# 171-5783_Redux.net
KiCad netlist of a schematic drawn in Altium Designer
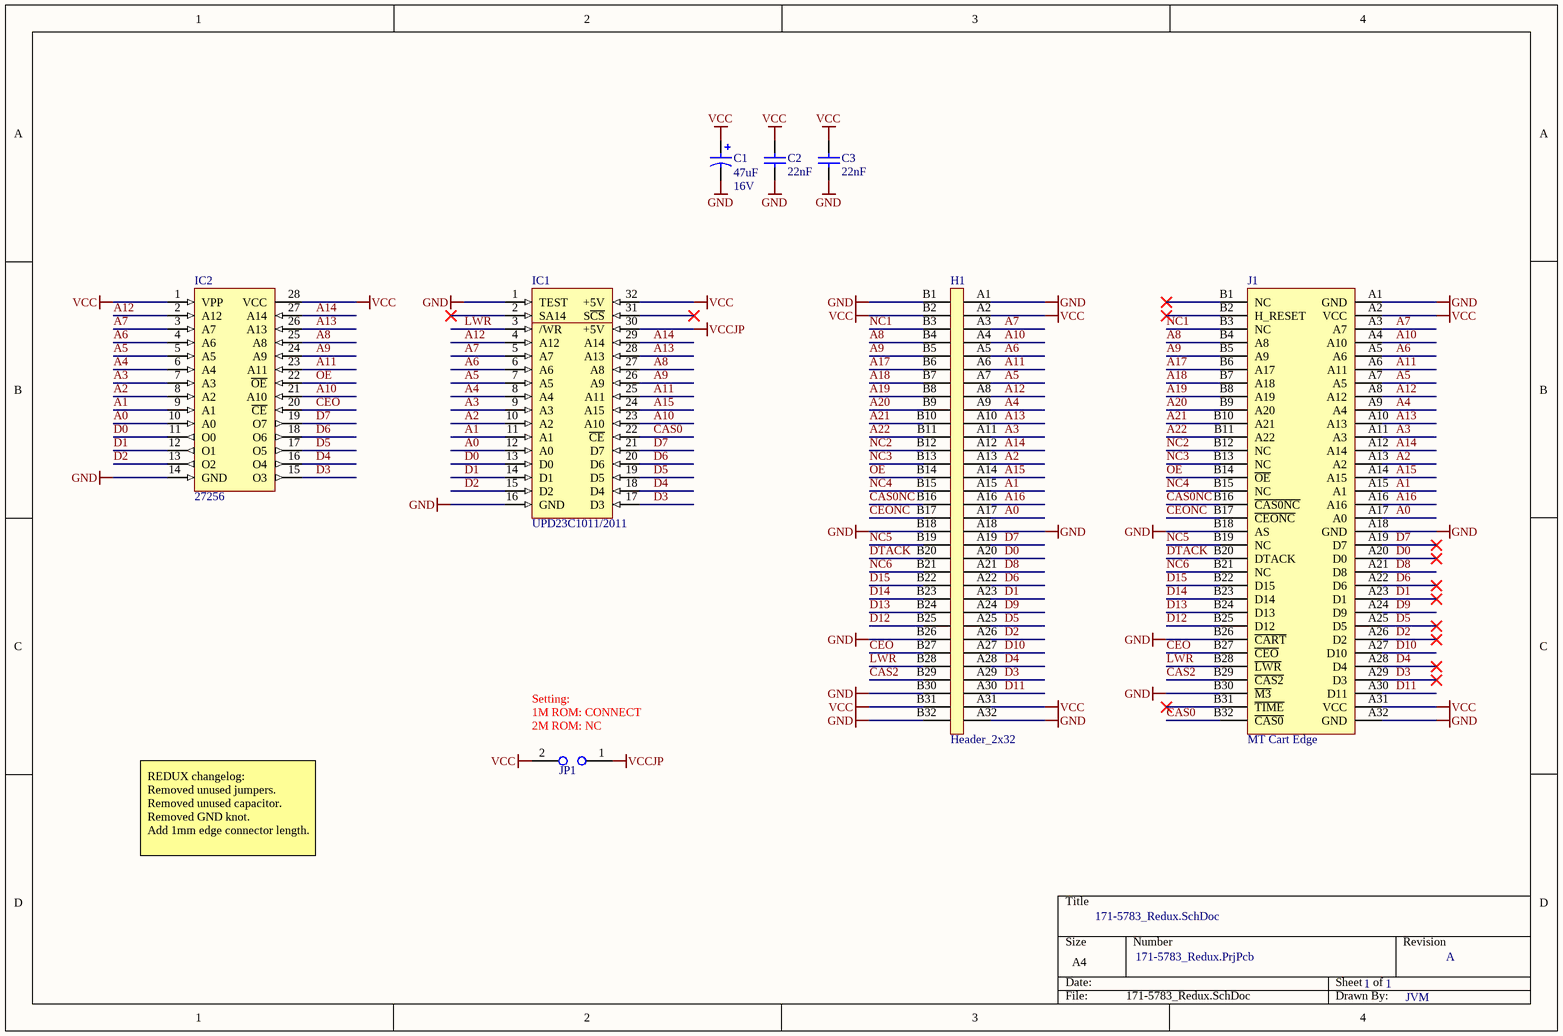
[diagram p0: 171-5783_Redux.SchDoc]

(export (version "E")
  (design (tool "Eeschema 10.0.6"))
  (components
    (comp (ref "C1")
      (value "47uF")
      (footprint "CapPol Mirror")
      (description "Polarized Capacitor, 2.54mm Pitch, 5mm Width, mirrored")
      (fields (field (name "VOLTAGE") "16V") (field (name "Comment") "Cap2.54P5.0D"))
      (libsource (lib "171-5782") (part "Cap2.54P5.0D_mirror"))
    )
    (comp (ref "C2")
      (value "22nF")
      (footprint "CapCer")
      (description "Capacitor (THT), Ceramic, 5.08mm Pitch")
      (fields (field (name "Comment") "CapCer"))
      (libsource (lib "171-5782") (part "CapCer"))
    )
    (comp (ref "C3")
      (value "22nF")
      (footprint "CapCer")
      (description "Capacitor (THT), Ceramic, 5.08mm Pitch")
      (fields (field (name "Comment") "CapCer"))
      (libsource (lib "171-5782") (part "CapCer"))
    )
    (comp (ref "H1")
      (value "Header_2x32")
      (footprint "Header_2x32")
      (libsource (lib "171-5782") (part "Header_2x32"))
    )
    (comp (ref "IC1")
      (value "UPD23C1011/2011")
      (footprint "UPD23C1011/2011")
      (description "SMS Mapper Mask Rom, Dual footprint")
      (libsource (lib "171-5782") (part "UPD23C1011/2011"))
    )
    (comp (ref "IC2")
      (value "27256")
      (footprint "27256")
      (description "256K EPROM")
      (libsource (lib "171-5782") (part "27256"))
    )
    (comp (ref "J1")
      (value "MT Cart Edge")
      (footprint "MT_Cart_Edge")
      (libsource (lib "171-5782") (part "MT_CART_EDGE_CON"))
    )
    (comp (ref "JP1")
      (value "SolderBridge")
      (footprint "SOLDER_BRIDGE")
      (description "Solder Bridge")
      (libsource (lib "171-5782") (part "SolderBridge"))
    )
  )
  (nets
    (net (code "1") (name "/A0") (class "Default")
      (node (ref "H1") (pin "A17") (pintype "passive"))
      (node (ref "IC1") (pin "12") (pinfunction "A0_12") (pintype "input"))
      (node (ref "IC2") (pin "10") (pinfunction "A0_10") (pintype "input"))
      (node (ref "J1") (pin "A17") (pinfunction "A0_A17") (pintype "passive"))
    )
    (net (code "2") (name "/A1") (class "Default")
      (node (ref "H1") (pin "A15") (pintype "passive"))
      (node (ref "IC1") (pin "11") (pinfunction "A1_11") (pintype "input"))
      (node (ref "IC2") (pin "9") (pinfunction "A1_9") (pintype "input"))
      (node (ref "J1") (pin "A15") (pinfunction "A1_A15") (pintype "passive"))
    )
    (net (code "3") (name "/A2") (class "Default")
      (node (ref "H1") (pin "A13") (pintype "passive"))
      (node (ref "IC1") (pin "10") (pinfunction "A2_10") (pintype "input"))
      (node (ref "IC2") (pin "8") (pinfunction "A2_8") (pintype "input"))
      (node (ref "J1") (pin "A13") (pinfunction "A2_A13") (pintype "passive"))
    )
    (net (code "4") (name "/A3") (class "Default")
      (node (ref "H1") (pin "A11") (pintype "passive"))
      (node (ref "IC1") (pin "9") (pinfunction "A3_9") (pintype "input"))
      (node (ref "IC2") (pin "7") (pinfunction "A3_7") (pintype "input"))
      (node (ref "J1") (pin "A11") (pinfunction "A3_A11") (pintype "passive"))
    )
    (net (code "5") (name "/A4") (class "Default")
      (node (ref "H1") (pin "A9") (pintype "passive"))
      (node (ref "IC1") (pin "8") (pinfunction "A4_8") (pintype "input"))
      (node (ref "IC2") (pin "6") (pinfunction "A4_6") (pintype "input"))
      (node (ref "J1") (pin "A9") (pinfunction "A4_A9") (pintype "passive"))
    )
    (net (code "6") (name "/A5") (class "Default")
      (node (ref "H1") (pin "A7") (pintype "passive"))
      (node (ref "IC1") (pin "7") (pinfunction "A5_7") (pintype "input"))
      (node (ref "IC2") (pin "5") (pinfunction "A5_5") (pintype "input"))
      (node (ref "J1") (pin "A7") (pinfunction "A5_A7") (pintype "passive"))
    )
    (net (code "7") (name "/A6") (class "Default")
      (node (ref "H1") (pin "A5") (pintype "passive"))
      (node (ref "IC1") (pin "6") (pinfunction "A6_6") (pintype "input"))
      (node (ref "IC2") (pin "4") (pinfunction "A6_4") (pintype "input"))
      (node (ref "J1") (pin "A5") (pinfunction "A6_A5") (pintype "passive"))
    )
    (net (code "8") (name "/A7") (class "Default")
      (node (ref "H1") (pin "A3") (pintype "passive"))
      (node (ref "IC1") (pin "5") (pinfunction "A7_5") (pintype "input"))
      (node (ref "IC2") (pin "3") (pinfunction "A7_3") (pintype "input"))
      (node (ref "J1") (pin "A3") (pinfunction "A7_A3") (pintype "passive"))
    )
    (net (code "9") (name "/A8") (class "Default")
      (node (ref "H1") (pin "B4") (pintype "passive"))
      (node (ref "IC1") (pin "27") (pinfunction "A8_27") (pintype "input"))
      (node (ref "IC2") (pin "25") (pinfunction "A8_25") (pintype "input"))
      (node (ref "J1") (pin "B4") (pinfunction "A8_B4") (pintype "passive"))
    )
    (net (code "10") (name "/A9") (class "Default")
      (node (ref "H1") (pin "B5") (pintype "passive"))
      (node (ref "IC1") (pin "26") (pinfunction "A9_26") (pintype "input"))
      (node (ref "IC2") (pin "24") (pinfunction "A9_24") (pintype "input"))
      (node (ref "J1") (pin "B5") (pinfunction "A9_B5") (pintype "passive"))
    )
    (net (code "11") (name "/A10") (class "Default")
      (node (ref "H1") (pin "A4") (pintype "passive"))
      (node (ref "IC1") (pin "23") (pinfunction "A10_23") (pintype "input"))
      (node (ref "IC2") (pin "21") (pinfunction "A10_21") (pintype "input"))
      (node (ref "J1") (pin "A4") (pinfunction "A10_A4") (pintype "passive"))
    )
    (net (code "12") (name "/A11") (class "Default")
      (node (ref "H1") (pin "A6") (pintype "passive"))
      (node (ref "IC1") (pin "25") (pinfunction "A11_25") (pintype "input"))
      (node (ref "IC2") (pin "23") (pinfunction "A11_23") (pintype "input"))
      (node (ref "J1") (pin "A6") (pinfunction "A11_A6") (pintype "passive"))
    )
    (net (code "13") (name "/A12") (class "Default")
      (node (ref "H1") (pin "A8") (pintype "passive"))
      (node (ref "IC1") (pin "4") (pinfunction "A12_4") (pintype "input"))
      (node (ref "IC2") (pin "2") (pinfunction "A12_2") (pintype "input"))
      (node (ref "J1") (pin "A8") (pinfunction "A12_A8") (pintype "passive"))
    )
    (net (code "14") (name "/A13") (class "Default")
      (node (ref "H1") (pin "A10") (pintype "passive"))
      (node (ref "IC1") (pin "28") (pinfunction "A13_28") (pintype "input"))
      (node (ref "IC2") (pin "26") (pinfunction "A13_26") (pintype "input"))
      (node (ref "J1") (pin "A10") (pinfunction "A13_A10") (pintype "passive"))
    )
    (net (code "15") (name "/A14") (class "Default")
      (node (ref "H1") (pin "A12") (pintype "passive"))
      (node (ref "IC1") (pin "29") (pinfunction "A14_29") (pintype "input"))
      (node (ref "IC2") (pin "27") (pinfunction "A14_27") (pintype "input"))
      (node (ref "J1") (pin "A12") (pinfunction "A14_A12") (pintype "passive"))
    )
    (net (code "16") (name "/A15") (class "Default")
      (node (ref "H1") (pin "A14") (pintype "passive"))
      (node (ref "IC1") (pin "24") (pinfunction "A15_24") (pintype "input"))
      (node (ref "J1") (pin "A14") (pinfunction "A15_A14") (pintype "passive"))
    )
    (net (code "17") (name "/A16") (class "Default")
      (node (ref "H1") (pin "A16") (pintype "passive"))
      (node (ref "J1") (pin "A16") (pinfunction "A16_A16") (pintype "passive"))
    )
    (net (code "18") (name "/A17") (class "Default")
      (node (ref "H1") (pin "B6") (pintype "passive"))
      (node (ref "J1") (pin "B6") (pinfunction "A17_B6") (pintype "passive"))
    )
    (net (code "19") (name "/A18") (class "Default")
      (node (ref "H1") (pin "B7") (pintype "passive"))
      (node (ref "J1") (pin "B7") (pinfunction "A18_B7") (pintype "passive"))
    )
    (net (code "20") (name "/A19") (class "Default")
      (node (ref "H1") (pin "B8") (pintype "passive"))
      (node (ref "J1") (pin "B8") (pinfunction "A19_B8") (pintype "passive"))
    )
    (net (code "21") (name "/A20") (class "Default")
      (node (ref "H1") (pin "B9") (pintype "passive"))
      (node (ref "J1") (pin "B9") (pinfunction "A20_B9") (pintype "passive"))
    )
    (net (code "22") (name "/A21") (class "Default")
      (node (ref "H1") (pin "B10") (pintype "passive"))
      (node (ref "J1") (pin "B10") (pinfunction "A21_B10") (pintype "passive"))
    )
    (net (code "23") (name "/A22") (class "Default")
      (node (ref "H1") (pin "B11") (pintype "passive"))
      (node (ref "J1") (pin "B11") (pinfunction "A22_B11") (pintype "passive"))
    )
    (net (code "24") (name "/CAS0") (class "Default")
      (node (ref "IC1") (pin "22") (pinfunction "~{CE}_22") (pintype "input"))
      (node (ref "J1") (pin "B32") (pinfunction "~{CAS0}_B32") (pintype "passive"))
    )
    (net (code "25") (name "/CAS0NC") (class "Default")
      (node (ref "H1") (pin "B16") (pintype "passive"))
      (node (ref "J1") (pin "B16") (pinfunction "~{CAS0NC}_B16") (pintype "passive"))
    )
    (net (code "26") (name "/CAS2") (class "Default")
      (node (ref "H1") (pin "B29") (pintype "passive"))
      (node (ref "J1") (pin "B29") (pinfunction "~{CAS2}_B29") (pintype "passive"))
    )
    (net (code "27") (name "/CEO") (class "Default")
      (node (ref "H1") (pin "B27") (pintype "passive"))
      (node (ref "IC2") (pin "20") (pinfunction "~{CE}_20") (pintype "input"))
      (node (ref "J1") (pin "B27") (pinfunction "~{CEO}_B27") (pintype "passive"))
    )
    (net (code "28") (name "/CEONC") (class "Default")
      (node (ref "H1") (pin "B17") (pintype "passive"))
      (node (ref "J1") (pin "B17") (pinfunction "~{CEONC}_B17") (pintype "passive"))
    )
    (net (code "29") (name "/D0") (class "Default")
      (node (ref "H1") (pin "A20") (pintype "passive"))
      (node (ref "IC1") (pin "13") (pinfunction "D0_13") (pintype "input"))
      (node (ref "IC2") (pin "11") (pinfunction "O0_11") (pintype "output"))
      (node (ref "J1") (pin "A20") (pinfunction "D0_A20") (pintype "passive"))
    )
    (net (code "30") (name "/D1") (class "Default")
      (node (ref "H1") (pin "A23") (pintype "passive"))
      (node (ref "IC1") (pin "14") (pinfunction "D1_14") (pintype "input"))
      (node (ref "IC2") (pin "12") (pinfunction "O1_12") (pintype "output"))
      (node (ref "J1") (pin "A23") (pinfunction "D1_A23") (pintype "passive"))
    )
    (net (code "31") (name "/D2") (class "Default")
      (node (ref "H1") (pin "A26") (pintype "passive"))
      (node (ref "IC1") (pin "15") (pinfunction "D2_15") (pintype "input"))
      (node (ref "IC2") (pin "13") (pinfunction "O2_13") (pintype "output"))
      (node (ref "J1") (pin "A26") (pinfunction "D2_A26") (pintype "passive"))
    )
    (net (code "32") (name "/D3") (class "Default")
      (node (ref "H1") (pin "A29") (pintype "passive"))
      (node (ref "IC1") (pin "17") (pinfunction "D3_17") (pintype "input"))
      (node (ref "IC2") (pin "15") (pinfunction "O3_15") (pintype "output"))
      (node (ref "J1") (pin "A29") (pinfunction "D3_A29") (pintype "passive"))
    )
    (net (code "33") (name "/D4") (class "Default")
      (node (ref "H1") (pin "A28") (pintype "passive"))
      (node (ref "IC1") (pin "18") (pinfunction "D4_18") (pintype "input"))
      (node (ref "IC2") (pin "16") (pinfunction "O4_16") (pintype "output"))
      (node (ref "J1") (pin "A28") (pinfunction "D4_A28") (pintype "passive"))
    )
    (net (code "34") (name "/D5") (class "Default")
      (node (ref "H1") (pin "A25") (pintype "passive"))
      (node (ref "IC1") (pin "19") (pinfunction "D5_19") (pintype "input"))
      (node (ref "IC2") (pin "17") (pinfunction "O5_17") (pintype "output"))
      (node (ref "J1") (pin "A25") (pinfunction "D5_A25") (pintype "passive"))
    )
    (net (code "35") (name "/D6") (class "Default")
      (node (ref "H1") (pin "A22") (pintype "passive"))
      (node (ref "IC1") (pin "20") (pinfunction "D6_20") (pintype "input"))
      (node (ref "IC2") (pin "18") (pinfunction "O6_18") (pintype "output"))
      (node (ref "J1") (pin "A22") (pinfunction "D6_A22") (pintype "passive"))
    )
    (net (code "36") (name "/D7") (class "Default")
      (node (ref "H1") (pin "A19") (pintype "passive"))
      (node (ref "IC1") (pin "21") (pinfunction "D7_21") (pintype "input"))
      (node (ref "IC2") (pin "19") (pinfunction "O7_19") (pintype "output"))
      (node (ref "J1") (pin "A19") (pinfunction "D7_A19") (pintype "passive"))
    )
    (net (code "37") (name "/D8") (class "Default")
      (node (ref "H1") (pin "A21") (pintype "passive"))
      (node (ref "J1") (pin "A21") (pinfunction "D8_A21") (pintype "passive"))
    )
    (net (code "38") (name "/D9") (class "Default")
      (node (ref "H1") (pin "A24") (pintype "passive"))
      (node (ref "J1") (pin "A24") (pinfunction "D9_A24") (pintype "passive"))
    )
    (net (code "39") (name "/D10") (class "Default")
      (node (ref "H1") (pin "A27") (pintype "passive"))
      (node (ref "J1") (pin "A27") (pinfunction "D10_A27") (pintype "passive"))
    )
    (net (code "40") (name "/D11") (class "Default")
      (node (ref "H1") (pin "A30") (pintype "passive"))
      (node (ref "J1") (pin "A30") (pinfunction "D11_A30") (pintype "passive"))
    )
    (net (code "41") (name "/D12") (class "Default")
      (node (ref "H1") (pin "B25") (pintype "passive"))
      (node (ref "J1") (pin "B25") (pinfunction "D12_B25") (pintype "passive"))
    )
    (net (code "42") (name "/D13") (class "Default")
      (node (ref "H1") (pin "B24") (pintype "passive"))
      (node (ref "J1") (pin "B24") (pinfunction "D13_B24") (pintype "passive"))
    )
    (net (code "43") (name "/D14") (class "Default")
      (node (ref "H1") (pin "B23") (pintype "passive"))
      (node (ref "J1") (pin "B23") (pinfunction "D14_B23") (pintype "passive"))
    )
    (net (code "44") (name "/D15") (class "Default")
      (node (ref "H1") (pin "B22") (pintype "passive"))
      (node (ref "J1") (pin "B22") (pinfunction "D15_B22") (pintype "passive"))
    )
    (net (code "45") (name "/DTACK") (class "Default")
      (node (ref "H1") (pin "B20") (pintype "passive"))
      (node (ref "J1") (pin "B20") (pinfunction "DTACK_B20") (pintype "passive"))
    )
    (net (code "46") (name "/LWR") (class "Default")
      (node (ref "H1") (pin "B28") (pintype "passive"))
      (node (ref "IC1") (pin "3") (pinfunction "/WR_3") (pintype "input"))
      (node (ref "J1") (pin "B28") (pinfunction "~{LWR}_B28") (pintype "passive"))
    )
    (net (code "47") (name "/NC1") (class "Default")
      (node (ref "H1") (pin "B3") (pintype "passive"))
      (node (ref "J1") (pin "B3") (pinfunction "NC_B3") (pintype "passive"))
    )
    (net (code "48") (name "/NC2") (class "Default")
      (node (ref "H1") (pin "B12") (pintype "passive"))
      (node (ref "J1") (pin "B12") (pinfunction "NC_B12") (pintype "passive"))
    )
    (net (code "49") (name "/NC3") (class "Default")
      (node (ref "H1") (pin "B13") (pintype "passive"))
      (node (ref "J1") (pin "B13") (pinfunction "NC_B13") (pintype "passive"))
    )
    (net (code "50") (name "/NC4") (class "Default")
      (node (ref "H1") (pin "B15") (pintype "passive"))
      (node (ref "J1") (pin "B15") (pinfunction "NC_B15") (pintype "passive"))
    )
    (net (code "51") (name "/NC5") (class "Default")
      (node (ref "H1") (pin "B19") (pintype "passive"))
      (node (ref "J1") (pin "B19") (pinfunction "NC_B19") (pintype "passive"))
    )
    (net (code "52") (name "/NC6") (class "Default")
      (node (ref "H1") (pin "B21") (pintype "passive"))
      (node (ref "J1") (pin "B21") (pinfunction "NC_B21") (pintype "passive"))
    )
    (net (code "53") (name "/OE") (class "Default")
      (node (ref "H1") (pin "B14") (pintype "passive"))
      (node (ref "IC2") (pin "22") (pinfunction "~{OE}_22") (pintype "input"))
      (node (ref "J1") (pin "B14") (pinfunction "~{OE}_B14") (pintype "passive"))
    )
    (net (code "54") (name "GND") (class "Default")
      (node (ref "C1") (pin "2") (pinfunction "2_2") (pintype "passive"))
      (node (ref "C2") (pin "1") (pinfunction "1_1") (pintype "passive"))
      (node (ref "C3") (pin "1") (pinfunction "1_1") (pintype "passive"))
      (node (ref "H1") (pin "A1") (pintype "passive"))
      (node (ref "H1") (pin "A18") (pintype "passive"))
      (node (ref "H1") (pin "A32") (pintype "passive"))
      (node (ref "H1") (pin "B1") (pintype "passive"))
      (node (ref "H1") (pin "B18") (pintype "passive"))
      (node (ref "H1") (pin "B26") (pintype "passive"))
      (node (ref "H1") (pin "B30") (pintype "passive"))
      (node (ref "H1") (pin "B32") (pintype "passive"))
      (node (ref "IC1") (pin "1") (pinfunction "TEST_1") (pintype "input"))
      (node (ref "IC1") (pin "16") (pinfunction "GND_16") (pintype "input"))
      (node (ref "IC2") (pin "14") (pinfunction "GND_14") (pintype "input"))
      (node (ref "J1") (pin "A1") (pinfunction "GND_A1") (pintype "passive"))
      (node (ref "J1") (pin "A18") (pinfunction "GND_A18") (pintype "passive"))
      (node (ref "J1") (pin "A32") (pinfunction "GND_A32") (pintype "passive"))
      (node (ref "J1") (pin "B18") (pinfunction "AS_B18") (pintype "passive"))
      (node (ref "J1") (pin "B26") (pinfunction "~{CART}_B26") (pintype "passive"))
      (node (ref "J1") (pin "B30") (pinfunction "~{M3}_B30") (pintype "passive"))
    )
    (net (code "55") (name "VCC") (class "Default")
      (node (ref "C1") (pin "1") (pinfunction "1_1") (pintype "passive"))
      (node (ref "C2") (pin "2") (pinfunction "2_2") (pintype "passive"))
      (node (ref "C3") (pin "2") (pinfunction "2_2") (pintype "passive"))
      (node (ref "H1") (pin "A2") (pintype "passive"))
      (node (ref "H1") (pin "A31") (pintype "passive"))
      (node (ref "H1") (pin "B2") (pintype "passive"))
      (node (ref "H1") (pin "B31") (pintype "passive"))
      (node (ref "IC1") (pin "32") (pinfunction "+5V_32") (pintype "input"))
      (node (ref "IC2") (pin "1") (pinfunction "VPP_1") (pintype "input"))
      (node (ref "IC2") (pin "28") (pinfunction "VCC_28") (pintype "power_in"))
      (node (ref "J1") (pin "A2") (pinfunction "VCC_A2") (pintype "passive"))
      (node (ref "J1") (pin "A31") (pinfunction "VCC_A31") (pintype "passive"))
      (node (ref "JP1") (pin "2") (pinfunction "2_2") (pintype "passive"))
    )
    (net (code "56") (name "VCCJP") (class "Default")
      (node (ref "IC1") (pin "30") (pinfunction "+5V_30") (pintype "input"))
      (node (ref "JP1") (pin "1") (pinfunction "1_1") (pintype "passive"))
    )
    (net (code "57") (name "unconnected-(IC1-SA14-Pad2)") (class "Default")
      (node (ref "IC1") (pin "2") (pinfunction "SA14_2") (pintype "input+no_connect"))
    )
    (net (code "58") (name "unconnected-(IC1-S~{CS}-Pad31)") (class "Default")
      (node (ref "IC1") (pin "31") (pinfunction "S~{CS}_31") (pintype "input+no_connect"))
    )
    (net (code "59") (name "unconnected-(J1-H_RESET-PadB2)") (class "Default")
      (node (ref "J1") (pin "B2") (pinfunction "H_RESET_B2") (pintype "passive+no_connect"))
    )
    (net (code "60") (name "unconnected-(J1-NC-PadB1)") (class "Default")
      (node (ref "J1") (pin "B1") (pinfunction "NC_B1") (pintype "passive+no_connect"))
    )
    (net (code "61") (name "unconnected-(J1-~{TIME}-PadB31)") (class "Default")
      (node (ref "J1") (pin "B31") (pinfunction "~{TIME}_B31") (pintype "passive+no_connect"))
    )
  )
)
